# Buck_Converter.net
KiCad netlist of a schematic drawn in Altium Designer
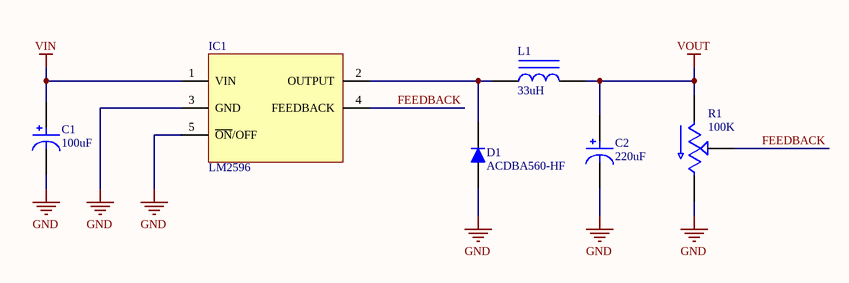
[diagram p0: Buck Converter.SchDoc]

(export (version "E")
  (design (tool "Eeschema 10.0.6"))
  (components
    (comp (ref "C1")
      (value "100uF")
      (footprint "RADIAL-2")
      (libsource (lib "Integrated_Library1") (part "100uF"))
    )
    (comp (ref "C2")
      (value "220uF")
      (footprint "RADIAL-2")
      (libsource (lib "Integrated_Library1") (part "220uF"))
    )
    (comp (ref "D1")
      (value "ACDBA560-HF")
      (footprint "DO-214")
      (libsource (lib "Integrated_Library1") (part "ACDBA560-HF"))
    )
    (comp (ref "IC1")
      (value "LM2596")
      (footprint "D2PAK")
      (libsource (lib "Integrated_Library1") (part "LM2596"))
    )
    (comp (ref "L1")
      (value "33uH")
      (footprint "SRR-1280")
      (libsource (lib "Integrated_Library1") (part "33uH"))
    )
    (comp (ref "R1") (value "100K") (footprint "3292W") (libsource (lib "Buck Converter") (part "100K")))
  )
  (nets
    (net (code "1") (name "/FEEDBACK") (class "Default")
      (node (ref "IC1") (pin "4") (pinfunction "FEEDBACK_4") (pintype "passive"))
      (node (ref "R1") (pin "2") (pinfunction "2_2") (pintype "passive"))
    )
    (net (code "2") (name "GND") (class "Default")
      (node (ref "C1") (pin "2") (pinfunction "2_2") (pintype "passive"))
      (node (ref "C2") (pin "2") (pinfunction "2_2") (pintype "passive"))
      (node (ref "D1") (pin "1") (pinfunction "1_1") (pintype "passive"))
      (node (ref "IC1") (pin "3") (pinfunction "GND_3") (pintype "passive"))
      (node (ref "IC1") (pin "5") (pinfunction "~{ON}/OFF_5") (pintype "passive"))
      (node (ref "R1") (pin "3") (pinfunction "3_3") (pintype "passive"))
    )
    (net (code "3") (name "Net-(IC1-OUTPUT)") (class "Default")
      (node (ref "D1") (pin "2") (pinfunction "2_2") (pintype "passive"))
      (node (ref "IC1") (pin "2") (pinfunction "OUTPUT_2") (pintype "passive"))
      (node (ref "L1") (pin "1") (pinfunction "1_1") (pintype "passive"))
    )
    (net (code "4") (name "VIN") (class "Default")
      (node (ref "C1") (pin "1") (pinfunction "1_1") (pintype "passive"))
      (node (ref "IC1") (pin "1") (pinfunction "VIN_1") (pintype "passive"))
    )
    (net (code "5") (name "VOUT") (class "Default")
      (node (ref "C2") (pin "1") (pinfunction "1_1") (pintype "passive"))
      (node (ref "L1") (pin "2") (pinfunction "2_2") (pintype "passive"))
      (node (ref "R1") (pin "1") (pinfunction "1_1") (pintype "passive"))
    )
  )
)
